# omnibus_proto.net
KiCad netlist of a schematic drawn in EAGLE
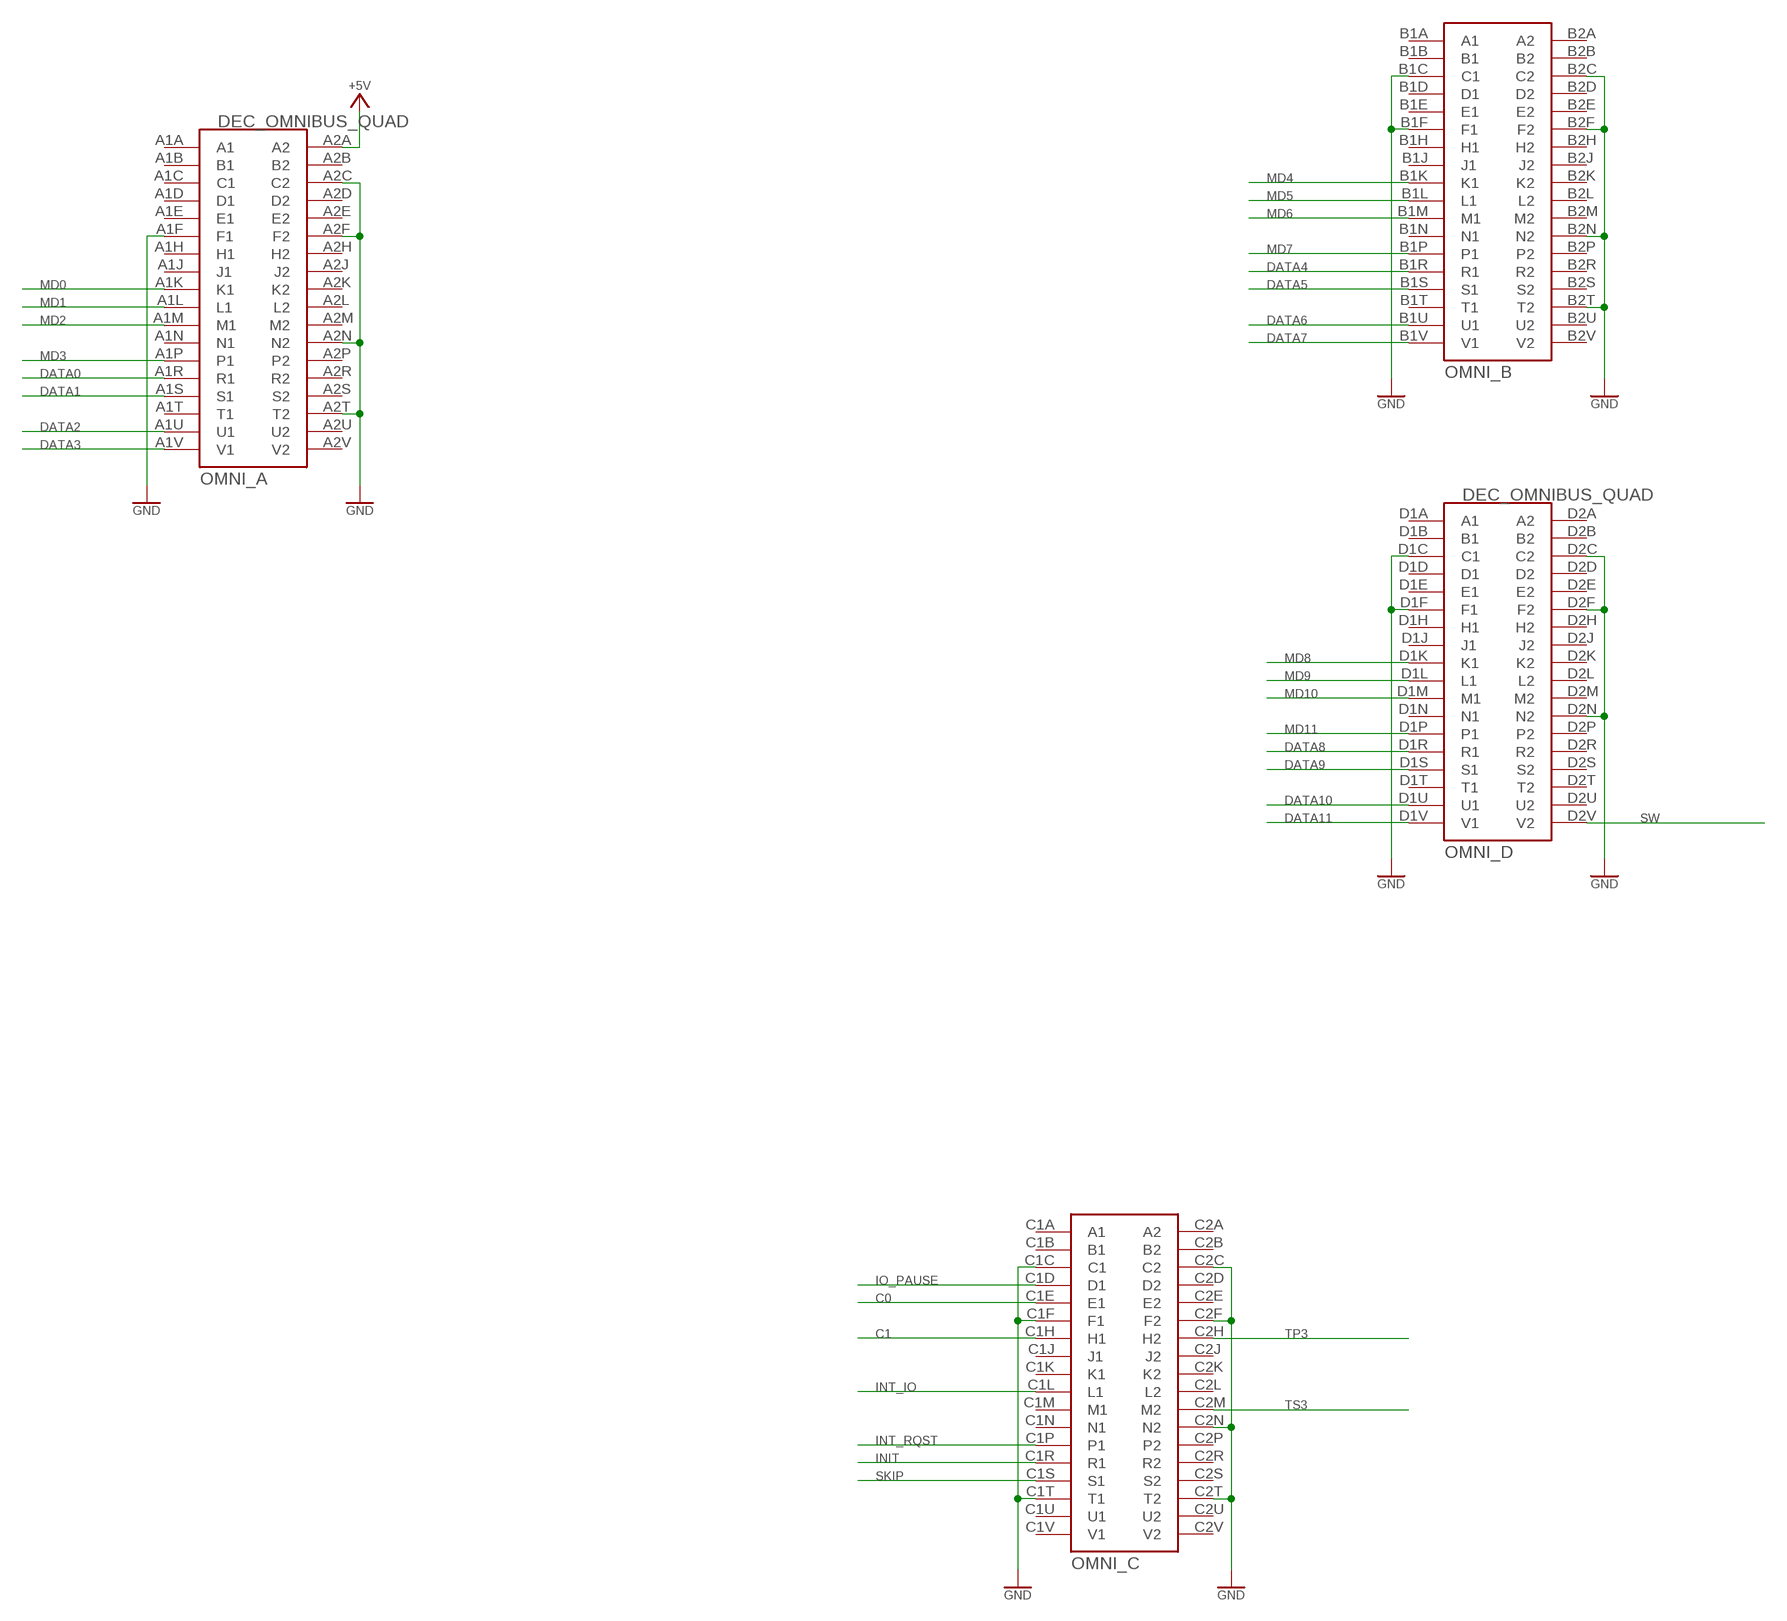
[diagram p0: schematic, sheet 1, part 1 of 2]
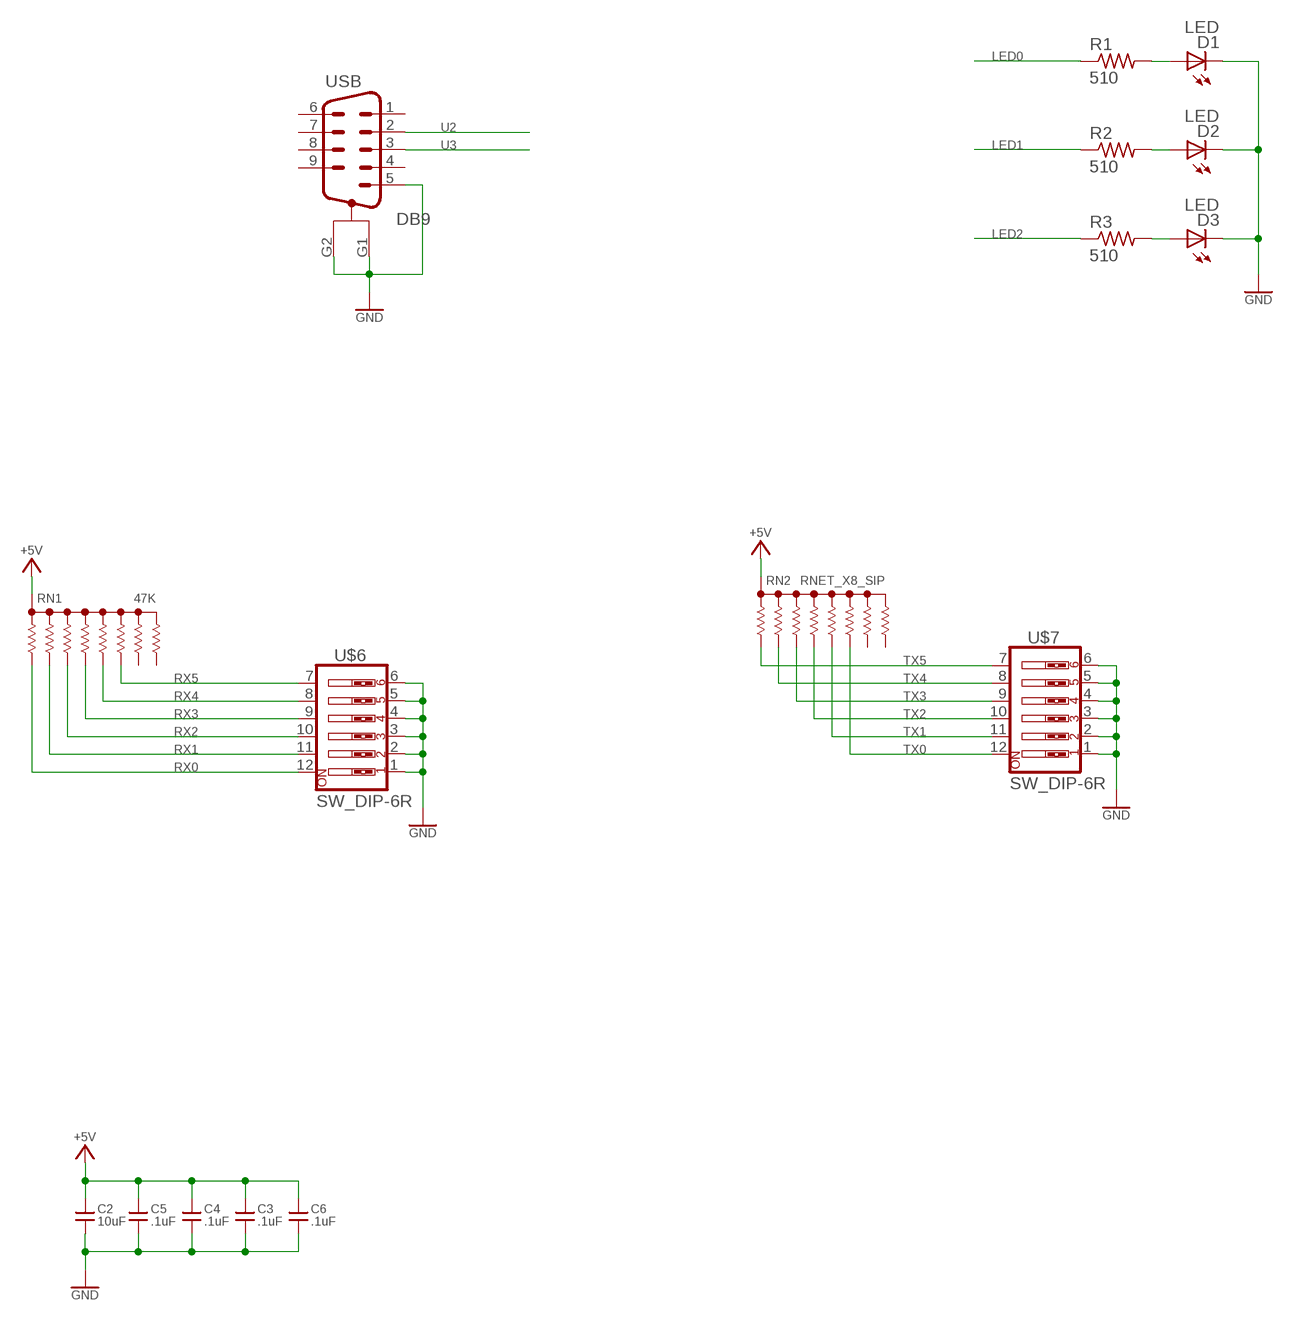
[diagram p1: schematic, sheet 1, part 2 of 2]
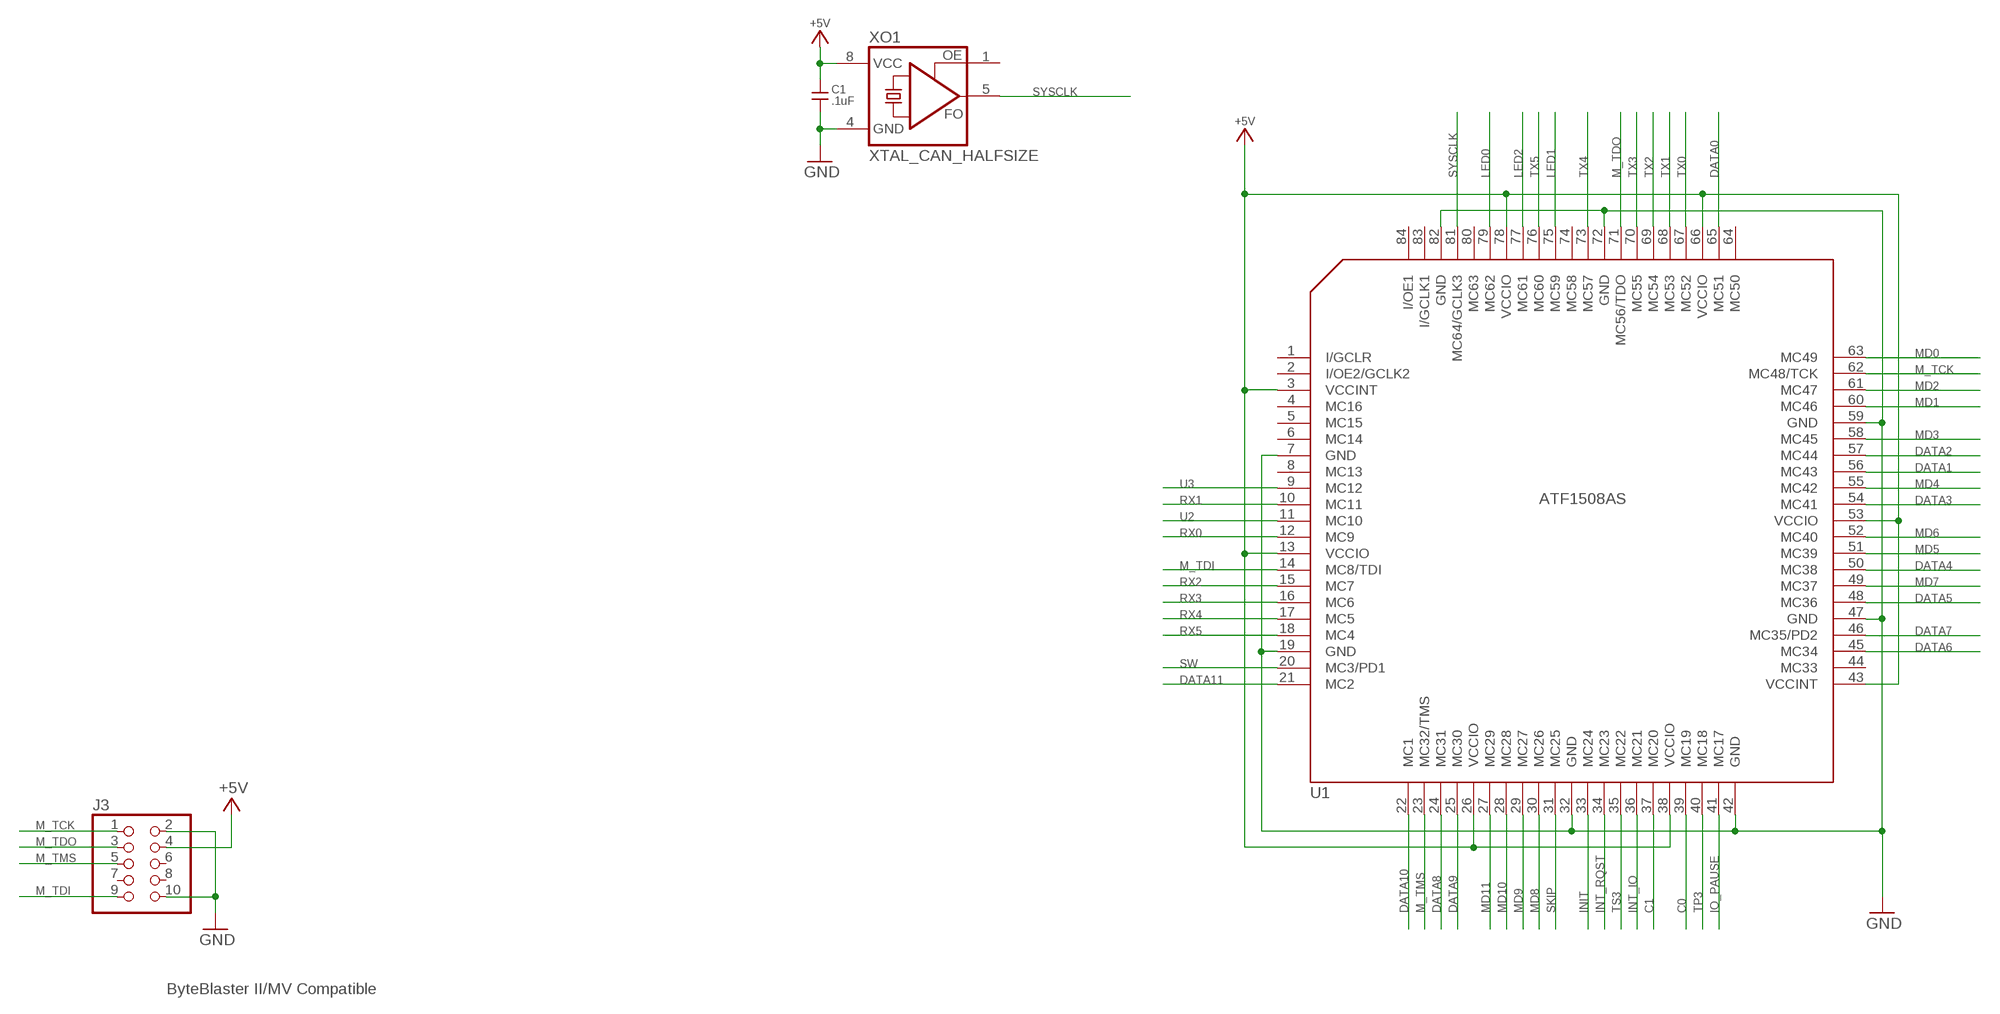
[diagram p2: schematic, sheet 2]

(export (version "E")
  (design (tool "Eeschema 10.0.6"))
  (components
    (comp (ref "C1")
      (value ".1uF")
      (footprint "eagle-import:C_TH_5MM")
      (libsource (lib "eagle-import") (part "C_US"))
    )
    (comp (ref "J3")
      (value "HDR_2X5\"")
      (footprint "eagle-import:HDR_2X5")
      (libsource (lib "eagle-import") (part "HDR_2X5{dblquote}"))
    )
    (comp (ref "U1")
      (value "ATF1508AS")
      (footprint "eagle-import:PLCC84")
      (libsource (lib "eagle-import") (part "ATF1504AS_PLCC"))
    )
    (comp (ref "XO1")
      (value "XTAL_CAN_HALFSIZE")
      (footprint "eagle-import:XTAL_CAN_HALFSIZE")
      (libsource (lib "eagle-import") (part "XTAL_CAN_HALFSIZE"))
    )
    (comp (ref "C2")
      (value "10uF")
      (footprint "eagle-import:C_TH_5MM")
      (libsource (lib "eagle-import") (part "C_US"))
    )
    (comp (ref "C3")
      (value ".1uF")
      (footprint "eagle-import:C_TH_5MM")
      (libsource (lib "eagle-import") (part "C_US"))
    )
    (comp (ref "C4")
      (value ".1uF")
      (footprint "eagle-import:C_TH_5MM")
      (libsource (lib "eagle-import") (part "C_US"))
    )
    (comp (ref "C5")
      (value ".1uF")
      (footprint "eagle-import:C_TH_5MM")
      (libsource (lib "eagle-import") (part "C_US"))
    )
    (comp (ref "C6")
      (value ".1uF")
      (footprint "eagle-import:C_TH_5MM")
      (libsource (lib "eagle-import") (part "C_US"))
    )
    (comp (ref "D1")
      (value "LED")
      (footprint "eagle-import:LED_TH_3MM")
      (libsource (lib "eagle-import") (part "LED"))
    )
    (comp (ref "D2")
      (value "LED")
      (footprint "eagle-import:LED_TH_3MM")
      (libsource (lib "eagle-import") (part "LED"))
    )
    (comp (ref "D3")
      (value "LED")
      (footprint "eagle-import:LED_TH_3MM")
      (libsource (lib "eagle-import") (part "LED"))
    )
    (comp (ref "OMNI")
      (value "DEC_OMNIBUS_QUAD")
      (footprint "eagle-import:DEC_OMNIBUS_QUAD")
      (libsource (lib "eagle-import") (part "DEC_OMNIBUS_QUAD"))
    )
    (comp (ref "R1")
      (value "510")
      (footprint "eagle-import:R_204_7")
      (libsource (lib "eagle-import") (part "R_US"))
    )
    (comp (ref "R2")
      (value "510")
      (footprint "eagle-import:R_204_7")
      (libsource (lib "eagle-import") (part "R_US"))
    )
    (comp (ref "R3")
      (value "510")
      (footprint "eagle-import:R_204_7")
      (libsource (lib "eagle-import") (part "R_US"))
    )
    (comp (ref "RN1")
      (value "47K")
      (footprint "eagle-import:RN_SIP9")
      (libsource (lib "eagle-import") (part "RNET_X8_SIP"))
    )
    (comp (ref "RN2")
      (value "RNET_X8_SIP")
      (footprint "eagle-import:RN_SIP9")
      (libsource (lib "eagle-import") (part "RNET_X8_SIP"))
    )
    (comp (ref "U$6")
      (value "SW_DIP-6R")
      (footprint "eagle-import:SW_DIP-6_ROUND")
      (libsource (lib "eagle-import") (part "SW_DIP-6R"))
    )
    (comp (ref "U$7")
      (value "SW_DIP-6R")
      (footprint "eagle-import:SW_DIP-6_ROUND")
      (libsource (lib "eagle-import") (part "SW_DIP-6R"))
    )
    (comp (ref "USB")
      (value "DB9")
      (footprint "eagle-import:AMP_DB-9RA")
      (fields (field (name "MANF") "TE/AMP"))
      (libsource (lib "eagle-import") (part "DB9"))
    )
  )
  (nets
    (net (code "1") (name "+5V") (class "Default")
      (node (ref "C1") (pin "1") (pinfunction "1_1") (pintype "passive"))
      (node (ref "C2") (pin "1") (pinfunction "1_1") (pintype "passive"))
      (node (ref "C3") (pin "1") (pinfunction "1_1") (pintype "passive"))
      (node (ref "C4") (pin "1") (pinfunction "1_1") (pintype "passive"))
      (node (ref "C5") (pin "1") (pinfunction "1_1") (pintype "passive"))
      (node (ref "C6") (pin "1") (pinfunction "1_1") (pintype "passive"))
      (node (ref "J3") (pin "4") (pinfunction "4_4") (pintype "passive"))
      (node (ref "OMNI") (pin "A2A") (pinfunction "A2_A2A") (pintype "passive"))
      (node (ref "RN1") (pin "1") (pinfunction "1_1") (pintype "passive"))
      (node (ref "RN2") (pin "1") (pinfunction "1_1") (pintype "passive"))
      (node (ref "U1") (pin "13") (pinfunction "VCCIO_13") (pintype "bidirectional"))
      (node (ref "U1") (pin "26") (pinfunction "VCCIO_26") (pintype "bidirectional"))
      (node (ref "U1") (pin "3") (pinfunction "VCCINT_3") (pintype "bidirectional"))
      (node (ref "U1") (pin "38") (pinfunction "VCCIO_38") (pintype "bidirectional"))
      (node (ref "U1") (pin "43") (pinfunction "VCCINT_43") (pintype "bidirectional"))
      (node (ref "U1") (pin "53") (pinfunction "VCCIO_53") (pintype "bidirectional"))
      (node (ref "U1") (pin "66") (pinfunction "VCCIO_66") (pintype "bidirectional"))
      (node (ref "U1") (pin "78") (pinfunction "VCCIO_78") (pintype "bidirectional"))
      (node (ref "XO1") (pin "8") (pinfunction "VCC_8") (pintype "power_in"))
    )
    (net (code "2") (name "C0") (class "Default")
      (node (ref "OMNI") (pin "C1E") (pinfunction "E1_C1E") (pintype "passive"))
      (node (ref "U1") (pin "39") (pinfunction "MC19_39") (pintype "bidirectional"))
    )
    (net (code "3") (name "C1") (class "Default")
      (node (ref "OMNI") (pin "C1H") (pinfunction "H1_C1H") (pintype "passive"))
      (node (ref "U1") (pin "37") (pinfunction "MC20_37") (pintype "bidirectional"))
    )
    (net (code "4") (name "DATA0") (class "Default")
      (node (ref "OMNI") (pin "A1R") (pinfunction "R1_A1R") (pintype "passive"))
      (node (ref "U1") (pin "65") (pinfunction "MC51_65") (pintype "bidirectional"))
    )
    (net (code "5") (name "DATA1") (class "Default")
      (node (ref "OMNI") (pin "A1S") (pinfunction "S1_A1S") (pintype "passive"))
      (node (ref "U1") (pin "56") (pinfunction "MC43_56") (pintype "bidirectional"))
    )
    (net (code "6") (name "DATA2") (class "Default")
      (node (ref "OMNI") (pin "A1U") (pinfunction "U1_A1U") (pintype "passive"))
      (node (ref "U1") (pin "57") (pinfunction "MC44_57") (pintype "bidirectional"))
    )
    (net (code "7") (name "DATA3") (class "Default")
      (node (ref "OMNI") (pin "A1V") (pinfunction "V1_A1V") (pintype "passive"))
      (node (ref "U1") (pin "54") (pinfunction "MC41_54") (pintype "bidirectional"))
    )
    (net (code "8") (name "DATA4") (class "Default")
      (node (ref "OMNI") (pin "B1R") (pinfunction "R1_B1R") (pintype "passive"))
      (node (ref "U1") (pin "50") (pinfunction "MC38_50") (pintype "bidirectional"))
    )
    (net (code "9") (name "DATA5") (class "Default")
      (node (ref "OMNI") (pin "B1S") (pinfunction "S1_B1S") (pintype "passive"))
      (node (ref "U1") (pin "48") (pinfunction "MC36_48") (pintype "bidirectional"))
    )
    (net (code "10") (name "DATA6") (class "Default")
      (node (ref "OMNI") (pin "B1U") (pinfunction "U1_B1U") (pintype "passive"))
      (node (ref "U1") (pin "45") (pinfunction "MC34_45") (pintype "bidirectional"))
    )
    (net (code "11") (name "DATA7") (class "Default")
      (node (ref "OMNI") (pin "B1V") (pinfunction "V1_B1V") (pintype "passive"))
      (node (ref "U1") (pin "46") (pinfunction "MC35/PD2_46") (pintype "bidirectional"))
    )
    (net (code "12") (name "DATA8") (class "Default")
      (node (ref "OMNI") (pin "D1R") (pinfunction "R1_D1R") (pintype "passive"))
      (node (ref "U1") (pin "24") (pinfunction "MC31_24") (pintype "bidirectional"))
    )
    (net (code "13") (name "DATA9") (class "Default")
      (node (ref "OMNI") (pin "D1S") (pinfunction "S1_D1S") (pintype "passive"))
      (node (ref "U1") (pin "25") (pinfunction "MC30_25") (pintype "bidirectional"))
    )
    (net (code "14") (name "DATA10") (class "Default")
      (node (ref "OMNI") (pin "D1U") (pinfunction "U1_D1U") (pintype "passive"))
      (node (ref "U1") (pin "22") (pinfunction "MC1_22") (pintype "bidirectional"))
    )
    (net (code "15") (name "DATA11") (class "Default")
      (node (ref "OMNI") (pin "D1V") (pinfunction "V1_D1V") (pintype "passive"))
      (node (ref "U1") (pin "21") (pinfunction "MC2_21") (pintype "bidirectional"))
    )
    (net (code "16") (name "GND") (class "Default")
      (node (ref "C1") (pin "2") (pinfunction "2_2") (pintype "passive"))
      (node (ref "C2") (pin "2") (pinfunction "2_2") (pintype "passive"))
      (node (ref "C3") (pin "2") (pinfunction "2_2") (pintype "passive"))
      (node (ref "C4") (pin "2") (pinfunction "2_2") (pintype "passive"))
      (node (ref "C5") (pin "2") (pinfunction "2_2") (pintype "passive"))
      (node (ref "C6") (pin "2") (pinfunction "2_2") (pintype "passive"))
      (node (ref "D1") (pin "K") (pinfunction "C_K") (pintype "passive"))
      (node (ref "D2") (pin "K") (pinfunction "C_K") (pintype "passive"))
      (node (ref "D3") (pin "K") (pinfunction "C_K") (pintype "passive"))
      (node (ref "J3") (pin "10") (pinfunction "10_10") (pintype "passive"))
      (node (ref "J3") (pin "2") (pinfunction "2_2") (pintype "passive"))
      (node (ref "OMNI") (pin "A1F") (pinfunction "F1_A1F") (pintype "passive"))
      (node (ref "OMNI") (pin "A2C") (pinfunction "C2_A2C") (pintype "passive"))
      (node (ref "OMNI") (pin "A2F") (pinfunction "F2_A2F") (pintype "passive"))
      (node (ref "OMNI") (pin "A2N") (pinfunction "N2_A2N") (pintype "passive"))
      (node (ref "OMNI") (pin "A2T") (pinfunction "T2_A2T") (pintype "passive"))
      (node (ref "OMNI") (pin "B1C") (pinfunction "C1_B1C") (pintype "passive"))
      (node (ref "OMNI") (pin "B1F") (pinfunction "F1_B1F") (pintype "passive"))
      (node (ref "OMNI") (pin "B2C") (pinfunction "C2_B2C") (pintype "passive"))
      (node (ref "OMNI") (pin "B2F") (pinfunction "F2_B2F") (pintype "passive"))
      (node (ref "OMNI") (pin "B2N") (pinfunction "N2_B2N") (pintype "passive"))
      (node (ref "OMNI") (pin "B2T") (pinfunction "T2_B2T") (pintype "passive"))
      (node (ref "OMNI") (pin "C1C") (pinfunction "C1_C1C") (pintype "passive"))
      (node (ref "OMNI") (pin "C1F") (pinfunction "F1_C1F") (pintype "passive"))
      (node (ref "OMNI") (pin "C1T") (pinfunction "T1_C1T") (pintype "passive"))
      (node (ref "OMNI") (pin "C2C") (pinfunction "C2_C2C") (pintype "passive"))
      (node (ref "OMNI") (pin "C2F") (pinfunction "F2_C2F") (pintype "passive"))
      (node (ref "OMNI") (pin "C2N") (pinfunction "N2_C2N") (pintype "passive"))
      (node (ref "OMNI") (pin "C2T") (pinfunction "T2_C2T") (pintype "passive"))
      (node (ref "OMNI") (pin "D1C") (pinfunction "C1_D1C") (pintype "passive"))
      (node (ref "OMNI") (pin "D1F") (pinfunction "F1_D1F") (pintype "passive"))
      (node (ref "OMNI") (pin "D2C") (pinfunction "C2_D2C") (pintype "passive"))
      (node (ref "OMNI") (pin "D2F") (pinfunction "F2_D2F") (pintype "passive"))
      (node (ref "OMNI") (pin "D2N") (pinfunction "N2_D2N") (pintype "passive"))
      (node (ref "U$6") (pin "1") (pinfunction "1_1") (pintype "passive"))
      (node (ref "U$6") (pin "2") (pinfunction "2_2") (pintype "passive"))
      (node (ref "U$6") (pin "3") (pinfunction "3_3") (pintype "passive"))
      (node (ref "U$6") (pin "4") (pinfunction "4_4") (pintype "passive"))
      (node (ref "U$6") (pin "5") (pinfunction "5_5") (pintype "passive"))
      (node (ref "U$6") (pin "6") (pinfunction "6_6") (pintype "passive"))
      (node (ref "U$7") (pin "1") (pinfunction "1_1") (pintype "passive"))
      (node (ref "U$7") (pin "2") (pinfunction "2_2") (pintype "passive"))
      (node (ref "U$7") (pin "3") (pinfunction "3_3") (pintype "passive"))
      (node (ref "U$7") (pin "4") (pinfunction "4_4") (pintype "passive"))
      (node (ref "U$7") (pin "5") (pinfunction "5_5") (pintype "passive"))
      (node (ref "U$7") (pin "6") (pinfunction "6_6") (pintype "passive"))
      (node (ref "U1") (pin "19") (pinfunction "GND_19") (pintype "bidirectional"))
      (node (ref "U1") (pin "32") (pinfunction "GND_32") (pintype "bidirectional"))
      (node (ref "U1") (pin "42") (pinfunction "GND_42") (pintype "bidirectional"))
      (node (ref "U1") (pin "47") (pinfunction "GND_47") (pintype "bidirectional"))
      (node (ref "U1") (pin "59") (pinfunction "GND_59") (pintype "bidirectional"))
      (node (ref "U1") (pin "7") (pinfunction "GND_7") (pintype "bidirectional"))
      (node (ref "U1") (pin "72") (pinfunction "GND_72") (pintype "bidirectional"))
      (node (ref "U1") (pin "82") (pinfunction "GND_82") (pintype "bidirectional"))
      (node (ref "USB") (pin "5") (pinfunction "5_5") (pintype "passive"))
      (node (ref "USB") (pin "G1") (pinfunction "G1_G1") (pintype "passive"))
      (node (ref "USB") (pin "G2") (pinfunction "G2_G2") (pintype "passive"))
      (node (ref "XO1") (pin "4") (pinfunction "GND_4") (pintype "power_in"))
    )
    (net (code "17") (name "INIT") (class "Default")
      (node (ref "OMNI") (pin "C1R") (pinfunction "R1_C1R") (pintype "passive"))
      (node (ref "U1") (pin "33") (pinfunction "MC24_33") (pintype "bidirectional"))
    )
    (net (code "18") (name "INT_IO") (class "Default")
      (node (ref "OMNI") (pin "C1L") (pinfunction "L1_C1L") (pintype "passive"))
      (node (ref "U1") (pin "36") (pinfunction "MC21_36") (pintype "bidirectional"))
    )
    (net (code "19") (name "INT_RQST") (class "Default")
      (node (ref "OMNI") (pin "C1P") (pinfunction "P1_C1P") (pintype "passive"))
      (node (ref "U1") (pin "34") (pinfunction "MC23_34") (pintype "bidirectional"))
    )
    (net (code "20") (name "IO_PAUSE") (class "Default")
      (node (ref "OMNI") (pin "C1D") (pinfunction "D1_C1D") (pintype "passive"))
      (node (ref "U1") (pin "41") (pinfunction "MC17_41") (pintype "bidirectional"))
    )
    (net (code "21") (name "LED0") (class "Default")
      (node (ref "R1") (pin "1") (pinfunction "1_1") (pintype "passive"))
      (node (ref "U1") (pin "79") (pinfunction "MC62_79") (pintype "bidirectional"))
    )
    (net (code "22") (name "LED1") (class "Default")
      (node (ref "R2") (pin "1") (pinfunction "1_1") (pintype "passive"))
      (node (ref "U1") (pin "75") (pinfunction "MC59_75") (pintype "bidirectional"))
    )
    (net (code "23") (name "LED2") (class "Default")
      (node (ref "R3") (pin "1") (pinfunction "1_1") (pintype "passive"))
      (node (ref "U1") (pin "77") (pinfunction "MC61_77") (pintype "bidirectional"))
    )
    (net (code "24") (name "MD0") (class "Default")
      (node (ref "OMNI") (pin "A1K") (pinfunction "K1_A1K") (pintype "passive"))
      (node (ref "U1") (pin "63") (pinfunction "MC49_63") (pintype "bidirectional"))
    )
    (net (code "25") (name "MD1") (class "Default")
      (node (ref "OMNI") (pin "A1L") (pinfunction "L1_A1L") (pintype "passive"))
      (node (ref "U1") (pin "60") (pinfunction "MC46_60") (pintype "bidirectional"))
    )
    (net (code "26") (name "MD2") (class "Default")
      (node (ref "OMNI") (pin "A1M") (pinfunction "M1_A1M") (pintype "passive"))
      (node (ref "U1") (pin "61") (pinfunction "MC47_61") (pintype "bidirectional"))
    )
    (net (code "27") (name "MD3") (class "Default")
      (node (ref "OMNI") (pin "A1P") (pinfunction "P1_A1P") (pintype "passive"))
      (node (ref "U1") (pin "58") (pinfunction "MC45_58") (pintype "bidirectional"))
    )
    (net (code "28") (name "MD4") (class "Default")
      (node (ref "OMNI") (pin "B1K") (pinfunction "K1_B1K") (pintype "passive"))
      (node (ref "U1") (pin "55") (pinfunction "MC42_55") (pintype "bidirectional"))
    )
    (net (code "29") (name "MD5") (class "Default")
      (node (ref "OMNI") (pin "B1L") (pinfunction "L1_B1L") (pintype "passive"))
      (node (ref "U1") (pin "51") (pinfunction "MC39_51") (pintype "bidirectional"))
    )
    (net (code "30") (name "MD6") (class "Default")
      (node (ref "OMNI") (pin "B1M") (pinfunction "M1_B1M") (pintype "passive"))
      (node (ref "U1") (pin "52") (pinfunction "MC40_52") (pintype "bidirectional"))
    )
    (net (code "31") (name "MD7") (class "Default")
      (node (ref "OMNI") (pin "B1P") (pinfunction "P1_B1P") (pintype "passive"))
      (node (ref "U1") (pin "49") (pinfunction "MC37_49") (pintype "bidirectional"))
    )
    (net (code "32") (name "MD8") (class "Default")
      (node (ref "OMNI") (pin "D1K") (pinfunction "K1_D1K") (pintype "passive"))
      (node (ref "U1") (pin "30") (pinfunction "MC26_30") (pintype "bidirectional"))
    )
    (net (code "33") (name "MD9") (class "Default")
      (node (ref "OMNI") (pin "D1L") (pinfunction "L1_D1L") (pintype "passive"))
      (node (ref "U1") (pin "29") (pinfunction "MC27_29") (pintype "bidirectional"))
    )
    (net (code "34") (name "MD10") (class "Default")
      (node (ref "OMNI") (pin "D1M") (pinfunction "M1_D1M") (pintype "passive"))
      (node (ref "U1") (pin "28") (pinfunction "MC28_28") (pintype "bidirectional"))
    )
    (net (code "35") (name "MD11") (class "Default")
      (node (ref "OMNI") (pin "D1P") (pinfunction "P1_D1P") (pintype "passive"))
      (node (ref "U1") (pin "27") (pinfunction "MC29_27") (pintype "bidirectional"))
    )
    (net (code "36") (name "M_TCK") (class "Default")
      (node (ref "J3") (pin "1") (pinfunction "1_1") (pintype "passive"))
      (node (ref "U1") (pin "62") (pinfunction "MC48/TCK_62") (pintype "bidirectional"))
    )
    (net (code "37") (name "M_TDI") (class "Default")
      (node (ref "J3") (pin "9") (pinfunction "9_9") (pintype "passive"))
      (node (ref "U1") (pin "14") (pinfunction "MC8/TDI_14") (pintype "bidirectional"))
    )
    (net (code "38") (name "M_TDO") (class "Default")
      (node (ref "J3") (pin "3") (pinfunction "3_3") (pintype "passive"))
      (node (ref "U1") (pin "71") (pinfunction "MC56/TDO_71") (pintype "bidirectional"))
    )
    (net (code "39") (name "M_TMS") (class "Default")
      (node (ref "J3") (pin "5") (pinfunction "5_5") (pintype "passive"))
      (node (ref "U1") (pin "23") (pinfunction "MC32/TMS_23") (pintype "bidirectional"))
    )
    (net (code "40") (name "Net-(D1-PadA)") (class "Default")
      (node (ref "D1") (pin "A") (pinfunction "A_A") (pintype "passive"))
      (node (ref "R1") (pin "2") (pinfunction "2_2") (pintype "passive"))
    )
    (net (code "41") (name "Net-(D2-PadA)") (class "Default")
      (node (ref "D2") (pin "A") (pinfunction "A_A") (pintype "passive"))
      (node (ref "R2") (pin "2") (pinfunction "2_2") (pintype "passive"))
    )
    (net (code "42") (name "Net-(D3-PadA)") (class "Default")
      (node (ref "D3") (pin "A") (pinfunction "A_A") (pintype "passive"))
      (node (ref "R3") (pin "2") (pinfunction "2_2") (pintype "passive"))
    )
    (net (code "43") (name "RX0") (class "Default")
      (node (ref "RN1") (pin "2") (pinfunction "2_2") (pintype "passive"))
      (node (ref "U$6") (pin "12") (pinfunction "12_12") (pintype "passive"))
      (node (ref "U1") (pin "12") (pinfunction "MC9_12") (pintype "bidirectional"))
    )
    (net (code "44") (name "RX1") (class "Default")
      (node (ref "RN1") (pin "3") (pinfunction "3_3") (pintype "passive"))
      (node (ref "U$6") (pin "11") (pinfunction "11_11") (pintype "passive"))
      (node (ref "U1") (pin "10") (pinfunction "MC11_10") (pintype "bidirectional"))
    )
    (net (code "45") (name "RX2") (class "Default")
      (node (ref "RN1") (pin "4") (pinfunction "4_4") (pintype "passive"))
      (node (ref "U$6") (pin "10") (pinfunction "10_10") (pintype "passive"))
      (node (ref "U1") (pin "15") (pinfunction "MC7_15") (pintype "bidirectional"))
    )
    (net (code "46") (name "RX3") (class "Default")
      (node (ref "RN1") (pin "5") (pinfunction "5_5") (pintype "passive"))
      (node (ref "U$6") (pin "9") (pinfunction "9_9") (pintype "passive"))
      (node (ref "U1") (pin "16") (pinfunction "MC6_16") (pintype "bidirectional"))
    )
    (net (code "47") (name "RX4") (class "Default")
      (node (ref "RN1") (pin "6") (pinfunction "6_6") (pintype "passive"))
      (node (ref "U$6") (pin "8") (pinfunction "8_8") (pintype "passive"))
      (node (ref "U1") (pin "17") (pinfunction "MC5_17") (pintype "bidirectional"))
    )
    (net (code "48") (name "RX5") (class "Default")
      (node (ref "RN1") (pin "7") (pinfunction "7_7") (pintype "passive"))
      (node (ref "U$6") (pin "7") (pinfunction "7_7") (pintype "passive"))
      (node (ref "U1") (pin "18") (pinfunction "MC4_18") (pintype "bidirectional"))
    )
    (net (code "49") (name "SKIP") (class "Default")
      (node (ref "OMNI") (pin "C1S") (pinfunction "S1_C1S") (pintype "passive"))
      (node (ref "U1") (pin "31") (pinfunction "MC25_31") (pintype "bidirectional"))
    )
    (net (code "50") (name "SW") (class "Default")
      (node (ref "OMNI") (pin "D2V") (pinfunction "V2_D2V") (pintype "passive"))
      (node (ref "U1") (pin "20") (pinfunction "MC3/PD1_20") (pintype "bidirectional"))
    )
    (net (code "51") (name "SYSCLK") (class "Default")
      (node (ref "U1") (pin "81") (pinfunction "MC64/GCLK3_81") (pintype "bidirectional"))
      (node (ref "XO1") (pin "5") (pinfunction "FO_5") (pintype "output"))
    )
    (net (code "52") (name "TP3") (class "Default")
      (node (ref "OMNI") (pin "C2H") (pinfunction "H2_C2H") (pintype "passive"))
      (node (ref "U1") (pin "40") (pinfunction "MC18_40") (pintype "bidirectional"))
    )
    (net (code "53") (name "TS3") (class "Default")
      (node (ref "OMNI") (pin "C2M") (pinfunction "M2_C2M") (pintype "passive"))
      (node (ref "U1") (pin "35") (pinfunction "MC22_35") (pintype "bidirectional"))
    )
    (net (code "54") (name "TX0") (class "Default")
      (node (ref "RN2") (pin "7") (pinfunction "7_7") (pintype "passive"))
      (node (ref "U$7") (pin "12") (pinfunction "12_12") (pintype "passive"))
      (node (ref "U1") (pin "67") (pinfunction "MC52_67") (pintype "bidirectional"))
    )
    (net (code "55") (name "TX1") (class "Default")
      (node (ref "RN2") (pin "6") (pinfunction "6_6") (pintype "passive"))
      (node (ref "U$7") (pin "11") (pinfunction "11_11") (pintype "passive"))
      (node (ref "U1") (pin "68") (pinfunction "MC53_68") (pintype "bidirectional"))
    )
    (net (code "56") (name "TX2") (class "Default")
      (node (ref "RN2") (pin "5") (pinfunction "5_5") (pintype "passive"))
      (node (ref "U$7") (pin "10") (pinfunction "10_10") (pintype "passive"))
      (node (ref "U1") (pin "69") (pinfunction "MC54_69") (pintype "bidirectional"))
    )
    (net (code "57") (name "TX3") (class "Default")
      (node (ref "RN2") (pin "4") (pinfunction "4_4") (pintype "passive"))
      (node (ref "U$7") (pin "9") (pinfunction "9_9") (pintype "passive"))
      (node (ref "U1") (pin "70") (pinfunction "MC55_70") (pintype "bidirectional"))
    )
    (net (code "58") (name "TX4") (class "Default")
      (node (ref "RN2") (pin "3") (pinfunction "3_3") (pintype "passive"))
      (node (ref "U$7") (pin "8") (pinfunction "8_8") (pintype "passive"))
      (node (ref "U1") (pin "73") (pinfunction "MC57_73") (pintype "bidirectional"))
    )
    (net (code "59") (name "TX5") (class "Default")
      (node (ref "RN2") (pin "2") (pinfunction "2_2") (pintype "passive"))
      (node (ref "U$7") (pin "7") (pinfunction "7_7") (pintype "passive"))
      (node (ref "U1") (pin "76") (pinfunction "MC60_76") (pintype "bidirectional"))
    )
    (net (code "60") (name "U2") (class "Default")
      (node (ref "U1") (pin "11") (pinfunction "MC10_11") (pintype "bidirectional"))
      (node (ref "USB") (pin "2") (pinfunction "2_2") (pintype "passive"))
    )
    (net (code "61") (name "U3") (class "Default")
      (node (ref "U1") (pin "9") (pinfunction "MC12_9") (pintype "bidirectional"))
      (node (ref "USB") (pin "3") (pinfunction "3_3") (pintype "passive"))
    )
    (net (code "62") (name "unconnected-(J3-Pad6)") (class "Default")
      (node (ref "J3") (pin "6") (pinfunction "6_6") (pintype "passive"))
    )
    (net (code "63") (name "unconnected-(J3-Pad7)") (class "Default")
      (node (ref "J3") (pin "7") (pinfunction "7_7") (pintype "passive"))
    )
    (net (code "64") (name "unconnected-(J3-Pad8)") (class "Default")
      (node (ref "J3") (pin "8") (pinfunction "8_8") (pintype "passive"))
    )
    (net (code "65") (name "unconnected-(OMNIA-A1-PadA1A)") (class "Default")
      (node (ref "OMNI") (pin "A1A") (pinfunction "A1_A1A") (pintype "passive"))
    )
    (net (code "66") (name "unconnected-(OMNIA-B1-PadA1B)") (class "Default")
      (node (ref "OMNI") (pin "A1B") (pinfunction "B1_A1B") (pintype "passive"))
    )
    (net (code "67") (name "unconnected-(OMNIA-B2-PadA2B)") (class "Default")
      (node (ref "OMNI") (pin "A2B") (pinfunction "B2_A2B") (pintype "passive"))
    )
    (net (code "68") (name "unconnected-(OMNIA-C1-PadA1C)") (class "Default")
      (node (ref "OMNI") (pin "A1C") (pinfunction "C1_A1C") (pintype "passive"))
    )
    (net (code "69") (name "unconnected-(OMNIA-D1-PadA1D)") (class "Default")
      (node (ref "OMNI") (pin "A1D") (pinfunction "D1_A1D") (pintype "passive"))
    )
    (net (code "70") (name "unconnected-(OMNIA-D2-PadA2D)") (class "Default")
      (node (ref "OMNI") (pin "A2D") (pinfunction "D2_A2D") (pintype "passive"))
    )
    (net (code "71") (name "unconnected-(OMNIA-E1-PadA1E)") (class "Default")
      (node (ref "OMNI") (pin "A1E") (pinfunction "E1_A1E") (pintype "passive"))
    )
    (net (code "72") (name "unconnected-(OMNIA-E2-PadA2E)") (class "Default")
      (node (ref "OMNI") (pin "A2E") (pinfunction "E2_A2E") (pintype "passive"))
    )
    (net (code "73") (name "unconnected-(OMNIA-H1-PadA1H)") (class "Default")
      (node (ref "OMNI") (pin "A1H") (pinfunction "H1_A1H") (pintype "passive"))
    )
    (net (code "74") (name "unconnected-(OMNIA-H2-PadA2H)") (class "Default")
      (node (ref "OMNI") (pin "A2H") (pinfunction "H2_A2H") (pintype "passive"))
    )
    (net (code "75") (name "unconnected-(OMNIA-J1-PadA1J)") (class "Default")
      (node (ref "OMNI") (pin "A1J") (pinfunction "J1_A1J") (pintype "passive"))
    )
    (net (code "76") (name "unconnected-(OMNIA-J2-PadA2J)") (class "Default")
      (node (ref "OMNI") (pin "A2J") (pinfunction "J2_A2J") (pintype "passive"))
    )
    (net (code "77") (name "unconnected-(OMNIA-K2-PadA2K)") (class "Default")
      (node (ref "OMNI") (pin "A2K") (pinfunction "K2_A2K") (pintype "passive"))
    )
    (net (code "78") (name "unconnected-(OMNIA-L2-PadA2L)") (class "Default")
      (node (ref "OMNI") (pin "A2L") (pinfunction "L2_A2L") (pintype "passive"))
    )
    (net (code "79") (name "unconnected-(OMNIA-M2-PadA2M)") (class "Default")
      (node (ref "OMNI") (pin "A2M") (pinfunction "M2_A2M") (pintype "passive"))
    )
    (net (code "80") (name "unconnected-(OMNIA-N1-PadA1N)") (class "Default")
      (node (ref "OMNI") (pin "A1N") (pinfunction "N1_A1N") (pintype "passive"))
    )
    (net (code "81") (name "unconnected-(OMNIA-P2-PadA2P)") (class "Default")
      (node (ref "OMNI") (pin "A2P") (pinfunction "P2_A2P") (pintype "passive"))
    )
    (net (code "82") (name "unconnected-(OMNIA-R2-PadA2R)") (class "Default")
      (node (ref "OMNI") (pin "A2R") (pinfunction "R2_A2R") (pintype "passive"))
    )
    (net (code "83") (name "unconnected-(OMNIA-S2-PadA2S)") (class "Default")
      (node (ref "OMNI") (pin "A2S") (pinfunction "S2_A2S") (pintype "passive"))
    )
    (net (code "84") (name "unconnected-(OMNIA-T1-PadA1T)") (class "Default")
      (node (ref "OMNI") (pin "A1T") (pinfunction "T1_A1T") (pintype "passive"))
    )
    (net (code "85") (name "unconnected-(OMNIA-U2-PadA2U)") (class "Default")
      (node (ref "OMNI") (pin "A2U") (pinfunction "U2_A2U") (pintype "passive"))
    )
    (net (code "86") (name "unconnected-(OMNIA-V2-PadA2V)") (class "Default")
      (node (ref "OMNI") (pin "A2V") (pinfunction "V2_A2V") (pintype "passive"))
    )
    (net (code "87") (name "unconnected-(OMNIB-A1-PadB1A)") (class "Default")
      (node (ref "OMNI") (pin "B1A") (pinfunction "A1_B1A") (pintype "passive"))
    )
    (net (code "88") (name "unconnected-(OMNIB-A2-PadB2A)") (class "Default")
      (node (ref "OMNI") (pin "B2A") (pinfunction "A2_B2A") (pintype "passive"))
    )
    (net (code "89") (name "unconnected-(OMNIB-B1-PadB1B)") (class "Default")
      (node (ref "OMNI") (pin "B1B") (pinfunction "B1_B1B") (pintype "passive"))
    )
    (net (code "90") (name "unconnected-(OMNIB-B2-PadB2B)") (class "Default")
      (node (ref "OMNI") (pin "B2B") (pinfunction "B2_B2B") (pintype "passive"))
    )
    (net (code "91") (name "unconnected-(OMNIB-D1-PadB1D)") (class "Default")
      (node (ref "OMNI") (pin "B1D") (pinfunction "D1_B1D") (pintype "passive"))
    )
    (net (code "92") (name "unconnected-(OMNIB-D2-PadB2D)") (class "Default")
      (node (ref "OMNI") (pin "B2D") (pinfunction "D2_B2D") (pintype "passive"))
    )
    (net (code "93") (name "unconnected-(OMNIB-E1-PadB1E)") (class "Default")
      (node (ref "OMNI") (pin "B1E") (pinfunction "E1_B1E") (pintype "passive"))
    )
    (net (code "94") (name "unconnected-(OMNIB-E2-PadB2E)") (class "Default")
      (node (ref "OMNI") (pin "B2E") (pinfunction "E2_B2E") (pintype "passive"))
    )
    (net (code "95") (name "unconnected-(OMNIB-H1-PadB1H)") (class "Default")
      (node (ref "OMNI") (pin "B1H") (pinfunction "H1_B1H") (pintype "passive"))
    )
    (net (code "96") (name "unconnected-(OMNIB-H2-PadB2H)") (class "Default")
      (node (ref "OMNI") (pin "B2H") (pinfunction "H2_B2H") (pintype "passive"))
    )
    (net (code "97") (name "unconnected-(OMNIB-J1-PadB1J)") (class "Default")
      (node (ref "OMNI") (pin "B1J") (pinfunction "J1_B1J") (pintype "passive"))
    )
    (net (code "98") (name "unconnected-(OMNIB-J2-PadB2J)") (class "Default")
      (node (ref "OMNI") (pin "B2J") (pinfunction "J2_B2J") (pintype "passive"))
    )
    (net (code "99") (name "unconnected-(OMNIB-K2-PadB2K)") (class "Default")
      (node (ref "OMNI") (pin "B2K") (pinfunction "K2_B2K") (pintype "passive"))
    )
    (net (code "100") (name "unconnected-(OMNIB-L2-PadB2L)") (class "Default")
      (node (ref "OMNI") (pin "B2L") (pinfunction "L2_B2L") (pintype "passive"))
    )
    (net (code "101") (name "unconnected-(OMNIB-M2-PadB2M)") (class "Default")
      (node (ref "OMNI") (pin "B2M") (pinfunction "M2_B2M") (pintype "passive"))
    )
    (net (code "102") (name "unconnected-(OMNIB-N1-PadB1N)") (class "Default")
      (node (ref "OMNI") (pin "B1N") (pinfunction "N1_B1N") (pintype "passive"))
    )
    (net (code "103") (name "unconnected-(OMNIB-P2-PadB2P)") (class "Default")
      (node (ref "OMNI") (pin "B2P") (pinfunction "P2_B2P") (pintype "passive"))
    )
    (net (code "104") (name "unconnected-(OMNIB-R2-PadB2R)") (class "Default")
      (node (ref "OMNI") (pin "B2R") (pinfunction "R2_B2R") (pintype "passive"))
    )
    (net (code "105") (name "unconnected-(OMNIB-S2-PadB2S)") (class "Default")
      (node (ref "OMNI") (pin "B2S") (pinfunction "S2_B2S") (pintype "passive"))
    )
    (net (code "106") (name "unconnected-(OMNIB-T1-PadB1T)") (class "Default")
      (node (ref "OMNI") (pin "B1T") (pinfunction "T1_B1T") (pintype "passive"))
    )
    (net (code "107") (name "unconnected-(OMNIB-U2-PadB2U)") (class "Default")
      (node (ref "OMNI") (pin "B2U") (pinfunction "U2_B2U") (pintype "passive"))
    )
    (net (code "108") (name "unconnected-(OMNIB-V2-PadB2V)") (class "Default")
      (node (ref "OMNI") (pin "B2V") (pinfunction "V2_B2V") (pintype "passive"))
    )
    (net (code "109") (name "unconnected-(OMNIC-A1-PadC1A)") (class "Default")
      (node (ref "OMNI") (pin "C1A") (pinfunction "A1_C1A") (pintype "passive"))
    )
    (net (code "110") (name "unconnected-(OMNIC-A2-PadC2A)") (class "Default")
      (node (ref "OMNI") (pin "C2A") (pinfunction "A2_C2A") (pintype "passive"))
    )
    (net (code "111") (name "unconnected-(OMNIC-B1-PadC1B)") (class "Default")
      (node (ref "OMNI") (pin "C1B") (pinfunction "B1_C1B") (pintype "passive"))
    )
    (net (code "112") (name "unconnected-(OMNIC-B2-PadC2B)") (class "Default")
      (node (ref "OMNI") (pin "C2B") (pinfunction "B2_C2B") (pintype "passive"))
    )
    (net (code "113") (name "unconnected-(OMNIC-D2-PadC2D)") (class "Default")
      (node (ref "OMNI") (pin "C2D") (pinfunction "D2_C2D") (pintype "passive"))
    )
    (net (code "114") (name "unconnected-(OMNIC-E2-PadC2E)") (class "Default")
      (node (ref "OMNI") (pin "C2E") (pinfunction "E2_C2E") (pintype "passive"))
    )
    (net (code "115") (name "unconnected-(OMNIC-J1-PadC1J)") (class "Default")
      (node (ref "OMNI") (pin "C1J") (pinfunction "J1_C1J") (pintype "passive"))
    )
    (net (code "116") (name "unconnected-(OMNIC-J2-PadC2J)") (class "Default")
      (node (ref "OMNI") (pin "C2J") (pinfunction "J2_C2J") (pintype "passive"))
    )
    (net (code "117") (name "unconnected-(OMNIC-K1-PadC1K)") (class "Default")
      (node (ref "OMNI") (pin "C1K") (pinfunction "K1_C1K") (pintype "passive"))
    )
    (net (code "118") (name "unconnected-(OMNIC-K2-PadC2K)") (class "Default")
      (node (ref "OMNI") (pin "C2K") (pinfunction "K2_C2K") (pintype "passive"))
    )
    (net (code "119") (name "unconnected-(OMNIC-L2-PadC2L)") (class "Default")
      (node (ref "OMNI") (pin "C2L") (pinfunction "L2_C2L") (pintype "passive"))
    )
    (net (code "120") (name "unconnected-(OMNIC-M1-PadC1M)") (class "Default")
      (node (ref "OMNI") (pin "C1M") (pinfunction "M1_C1M") (pintype "passive"))
    )
    (net (code "121") (name "unconnected-(OMNIC-N1-PadC1N)") (class "Default")
      (node (ref "OMNI") (pin "C1N") (pinfunction "N1_C1N") (pintype "passive"))
    )
    (net (code "122") (name "unconnected-(OMNIC-P2-PadC2P)") (class "Default")
      (node (ref "OMNI") (pin "C2P") (pinfunction "P2_C2P") (pintype "passive"))
    )
    (net (code "123") (name "unconnected-(OMNIC-R2-PadC2R)") (class "Default")
      (node (ref "OMNI") (pin "C2R") (pinfunction "R2_C2R") (pintype "passive"))
    )
    (net (code "124") (name "unconnected-(OMNIC-S2-PadC2S)") (class "Default")
      (node (ref "OMNI") (pin "C2S") (pinfunction "S2_C2S") (pintype "passive"))
    )
    (net (code "125") (name "unconnected-(OMNIC-U1-PadC1U)") (class "Default")
      (node (ref "OMNI") (pin "C1U") (pinfunction "U1_C1U") (pintype "passive"))
    )
    (net (code "126") (name "unconnected-(OMNIC-U2-PadC2U)") (class "Default")
      (node (ref "OMNI") (pin "C2U") (pinfunction "U2_C2U") (pintype "passive"))
    )
    (net (code "127") (name "unconnected-(OMNIC-V1-PadC1V)") (class "Default")
      (node (ref "OMNI") (pin "C1V") (pinfunction "V1_C1V") (pintype "passive"))
    )
    (net (code "128") (name "unconnected-(OMNIC-V2-PadC2V)") (class "Default")
      (node (ref "OMNI") (pin "C2V") (pinfunction "V2_C2V") (pintype "passive"))
    )
    (net (code "129") (name "unconnected-(OMNID-A1-PadD1A)") (class "Default")
      (node (ref "OMNI") (pin "D1A") (pinfunction "A1_D1A") (pintype "passive"))
    )
    (net (code "130") (name "unconnected-(OMNID-A2-PadD2A)") (class "Default")
      (node (ref "OMNI") (pin "D2A") (pinfunction "A2_D2A") (pintype "passive"))
    )
    (net (code "131") (name "unconnected-(OMNID-B1-PadD1B)") (class "Default")
      (node (ref "OMNI") (pin "D1B") (pinfunction "B1_D1B") (pintype "passive"))
    )
    (net (code "132") (name "unconnected-(OMNID-B2-PadD2B)") (class "Default")
      (node (ref "OMNI") (pin "D2B") (pinfunction "B2_D2B") (pintype "passive"))
    )
    (net (code "133") (name "unconnected-(OMNID-D1-PadD1D)") (class "Default")
      (node (ref "OMNI") (pin "D1D") (pinfunction "D1_D1D") (pintype "passive"))
    )
    (net (code "134") (name "unconnected-(OMNID-D2-PadD2D)") (class "Default")
      (node (ref "OMNI") (pin "D2D") (pinfunction "D2_D2D") (pintype "passive"))
    )
    (net (code "135") (name "unconnected-(OMNID-E1-PadD1E)") (class "Default")
      (node (ref "OMNI") (pin "D1E") (pinfunction "E1_D1E") (pintype "passive"))
    )
    (net (code "136") (name "unconnected-(OMNID-E2-PadD2E)") (class "Default")
      (node (ref "OMNI") (pin "D2E") (pinfunction "E2_D2E") (pintype "passive"))
    )
    (net (code "137") (name "unconnected-(OMNID-H1-PadD1H)") (class "Default")
      (node (ref "OMNI") (pin "D1H") (pinfunction "H1_D1H") (pintype "passive"))
    )
    (net (code "138") (name "unconnected-(OMNID-H2-PadD2H)") (class "Default")
      (node (ref "OMNI") (pin "D2H") (pinfunction "H2_D2H") (pintype "passive"))
    )
    (net (code "139") (name "unconnected-(OMNID-J1-PadD1J)") (class "Default")
      (node (ref "OMNI") (pin "D1J") (pinfunction "J1_D1J") (pintype "passive"))
    )
    (net (code "140") (name "unconnected-(OMNID-J2-PadD2J)") (class "Default")
      (node (ref "OMNI") (pin "D2J") (pinfunction "J2_D2J") (pintype "passive"))
    )
    (net (code "141") (name "unconnected-(OMNID-K2-PadD2K)") (class "Default")
      (node (ref "OMNI") (pin "D2K") (pinfunction "K2_D2K") (pintype "passive"))
    )
    (net (code "142") (name "unconnected-(OMNID-L2-PadD2L)") (class "Default")
      (node (ref "OMNI") (pin "D2L") (pinfunction "L2_D2L") (pintype "passive"))
    )
    (net (code "143") (name "unconnected-(OMNID-M2-PadD2M)") (class "Default")
      (node (ref "OMNI") (pin "D2M") (pinfunction "M2_D2M") (pintype "passive"))
    )
    (net (code "144") (name "unconnected-(OMNID-N1-PadD1N)") (class "Default")
      (node (ref "OMNI") (pin "D1N") (pinfunction "N1_D1N") (pintype "passive"))
    )
    (net (code "145") (name "unconnected-(OMNID-P2-PadD2P)") (class "Default")
      (node (ref "OMNI") (pin "D2P") (pinfunction "P2_D2P") (pintype "passive"))
    )
    (net (code "146") (name "unconnected-(OMNID-R2-PadD2R)") (class "Default")
      (node (ref "OMNI") (pin "D2R") (pinfunction "R2_D2R") (pintype "passive"))
    )
    (net (code "147") (name "unconnected-(OMNID-S2-PadD2S)") (class "Default")
      (node (ref "OMNI") (pin "D2S") (pinfunction "S2_D2S") (pintype "passive"))
    )
    (net (code "148") (name "unconnected-(OMNID-T1-PadD1T)") (class "Default")
      (node (ref "OMNI") (pin "D1T") (pinfunction "T1_D1T") (pintype "passive"))
    )
    (net (code "149") (name "unconnected-(OMNID-T2-PadD2T)") (class "Default")
      (node (ref "OMNI") (pin "D2T") (pinfunction "T2_D2T") (pintype "passive"))
    )
    (net (code "150") (name "unconnected-(OMNID-U2-PadD2U)") (class "Default")
      (node (ref "OMNI") (pin "D2U") (pinfunction "U2_D2U") (pintype "passive"))
    )
    (net (code "151") (name "unconnected-(RN1-Pad8)") (class "Default")
      (node (ref "RN1") (pin "8") (pinfunction "8_8") (pintype "passive"))
    )
    (net (code "152") (name "unconnected-(RN1-Pad9)") (class "Default")
      (node (ref "RN1") (pin "9") (pinfunction "9_9") (pintype "passive"))
    )
    (net (code "153") (name "unconnected-(RN2-Pad8)") (class "Default")
      (node (ref "RN2") (pin "8") (pinfunction "8_8") (pintype "passive"))
    )
    (net (code "154") (name "unconnected-(RN2-Pad9)") (class "Default")
      (node (ref "RN2") (pin "9") (pinfunction "9_9") (pintype "passive"))
    )
    (net (code "155") (name "unconnected-(U1-I{slash}GCLK1-Pad83)") (class "Default")
      (node (ref "U1") (pin "83") (pinfunction "I/GCLK1_83") (pintype "bidirectional"))
    )
    (net (code "156") (name "unconnected-(U1-I{slash}GCLR-Pad1)") (class "Default")
      (node (ref "U1") (pin "1") (pinfunction "I/GCLR_1") (pintype "bidirectional"))
    )
    (net (code "157") (name "unconnected-(U1-I{slash}OE1-Pad84)") (class "Default")
      (node (ref "U1") (pin "84") (pinfunction "I/OE1_84") (pintype "bidirectional"))
    )
    (net (code "158") (name "unconnected-(U1-I{slash}OE2{slash}GCLK2-Pad2)") (class "Default")
      (node (ref "U1") (pin "2") (pinfunction "I/OE2/GCLK2_2") (pintype "bidirectional"))
    )
    (net (code "159") (name "unconnected-(U1-MC13-Pad8)") (class "Default")
      (node (ref "U1") (pin "8") (pinfunction "MC13_8") (pintype "bidirectional"))
    )
    (net (code "160") (name "unconnected-(U1-MC14-Pad6)") (class "Default")
      (node (ref "U1") (pin "6") (pinfunction "MC14_6") (pintype "bidirectional"))
    )
    (net (code "161") (name "unconnected-(U1-MC15-Pad5)") (class "Default")
      (node (ref "U1") (pin "5") (pinfunction "MC15_5") (pintype "bidirectional"))
    )
    (net (code "162") (name "unconnected-(U1-MC16-Pad4)") (class "Default")
      (node (ref "U1") (pin "4") (pinfunction "MC16_4") (pintype "bidirectional"))
    )
    (net (code "163") (name "unconnected-(U1-MC33-Pad44)") (class "Default")
      (node (ref "U1") (pin "44") (pinfunction "MC33_44") (pintype "bidirectional"))
    )
    (net (code "164") (name "unconnected-(U1-MC50-Pad64)") (class "Default")
      (node (ref "U1") (pin "64") (pinfunction "MC50_64") (pintype "bidirectional"))
    )
    (net (code "165") (name "unconnected-(U1-MC58-Pad74)") (class "Default")
      (node (ref "U1") (pin "74") (pinfunction "MC58_74") (pintype "bidirectional"))
    )
    (net (code "166") (name "unconnected-(U1-MC63-Pad80)") (class "Default")
      (node (ref "U1") (pin "80") (pinfunction "MC63_80") (pintype "bidirectional"))
    )
    (net (code "167") (name "unconnected-(USB-Pad1)") (class "Default")
      (node (ref "USB") (pin "1") (pinfunction "1_1") (pintype "passive"))
    )
    (net (code "168") (name "unconnected-(USB-Pad4)") (class "Default")
      (node (ref "USB") (pin "4") (pinfunction "4_4") (pintype "passive"))
    )
    (net (code "169") (name "unconnected-(USB-Pad6)") (class "Default")
      (node (ref "USB") (pin "6") (pinfunction "6_6") (pintype "passive"))
    )
    (net (code "170") (name "unconnected-(USB-Pad7)") (class "Default")
      (node (ref "USB") (pin "7") (pinfunction "7_7") (pintype "passive"))
    )
    (net (code "171") (name "unconnected-(USB-Pad8)") (class "Default")
      (node (ref "USB") (pin "8") (pinfunction "8_8") (pintype "passive"))
    )
    (net (code "172") (name "unconnected-(USB-Pad9)") (class "Default")
      (node (ref "USB") (pin "9") (pinfunction "9_9") (pintype "passive"))
    )
    (net (code "173") (name "unconnected-(XO1-OE-Pad1)") (class "Default")
      (node (ref "XO1") (pin "1") (pinfunction "OE_1") (pintype "input"))
    )
  )
)
